# USBLiPo.net
KiCad netlist of a schematic drawn in EAGLE
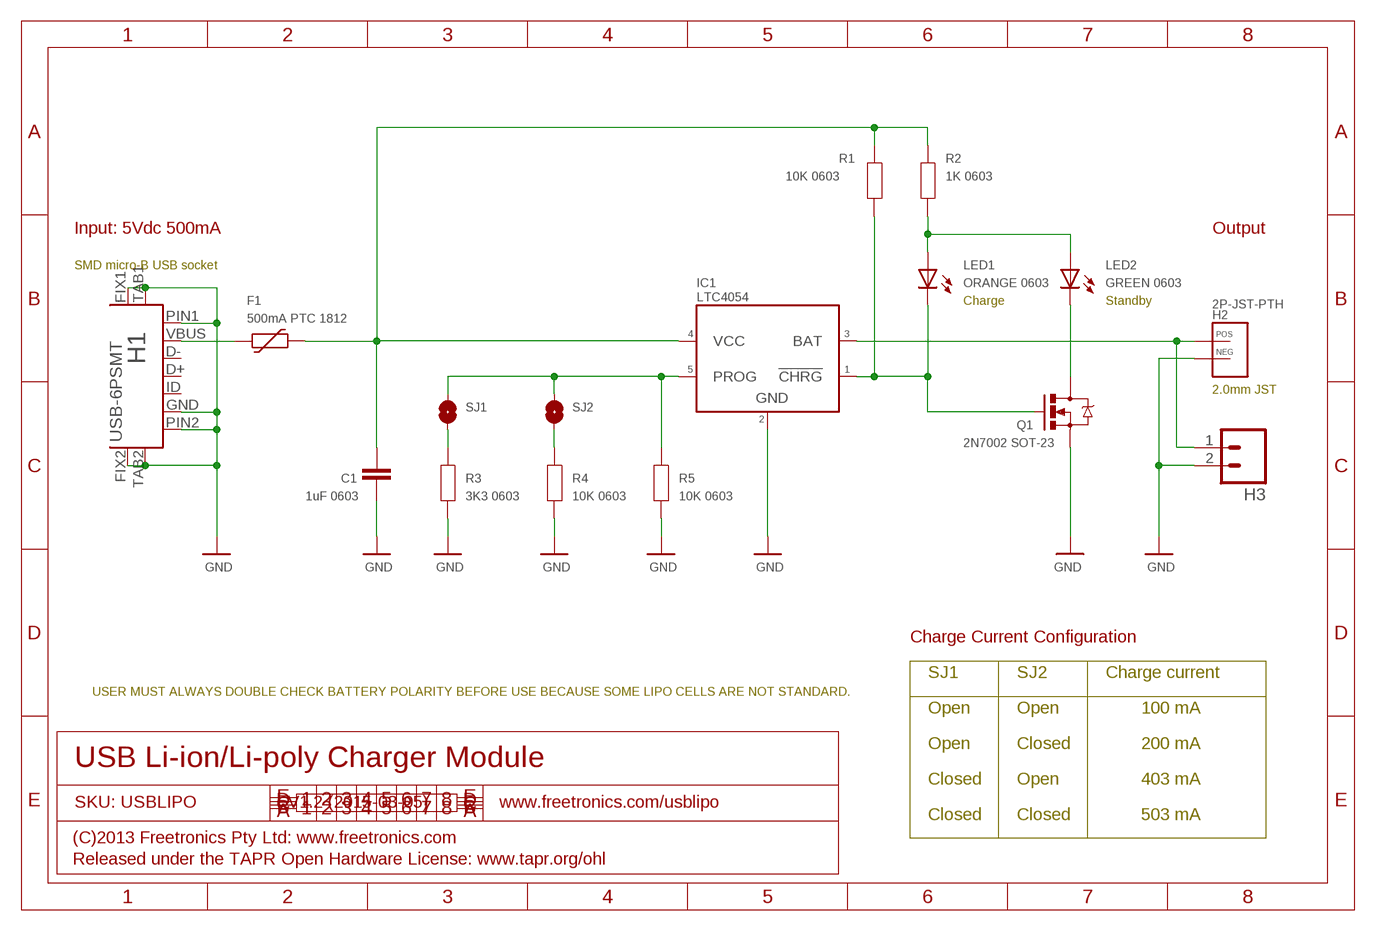
[diagram p0: schematic, sheet 1]

(export (version "E")
  (design (tool "Eeschema 10.0.6"))
  (components
    (comp (ref "C1")
      (value "1uF 0603")
      (footprint "eagle-import:0603")
      (libsource (lib "eagle-import") (part "CAP0603"))
    )
    (comp (ref "F1")
      (value "500mA PTC 1812")
      (footprint "eagle-import:1812")
      (libsource (lib "eagle-import") (part "PTC"))
    )
    (comp (ref "H1")
      (value "USB-6PSMT")
      (footprint "eagle-import:USB-MICROB-MB05PMXX")
      (libsource (lib "eagle-import") (part "USB-6PSMT"))
    )
    (comp (ref "H2")
      (value "2P-JST-PTH")
      (footprint "eagle-import:JST-2MM-TH-RA")
      (libsource (lib "eagle-import") (part "2P-JST-TH-RAPTH"))
    )
    (comp (ref "H3")
      (value "M02PTH")
      (footprint "eagle-import:1X02")
      (libsource (lib "eagle-import") (part "M02PTH"))
    )
    (comp (ref "IC1")
      (value "LTC4054")
      (footprint "eagle-import:SOT23-5")
      (libsource (lib "eagle-import") (part "LTC4054"))
    )
    (comp (ref "LED1")
      (value "ORANGE 0603")
      (footprint "eagle-import:LED-0603")
      (libsource (lib "eagle-import") (part "LED0603"))
    )
    (comp (ref "LED2")
      (value "GREEN 0603")
      (footprint "eagle-import:LED-0603")
      (libsource (lib "eagle-import") (part "LED0603"))
    )
    (comp (ref "Q1")
      (value "2N7002 SOT-23")
      (footprint "eagle-import:SOT23-3")
      (libsource (lib "eagle-import") (part "2N7002"))
    )
    (comp (ref "R1")
      (value "10K 0603")
      (footprint "eagle-import:0603")
      (libsource (lib "eagle-import") (part "RESISTOR0603"))
    )
    (comp (ref "R2")
      (value "1K 0603")
      (footprint "eagle-import:0603")
      (libsource (lib "eagle-import") (part "RESISTOR0603"))
    )
    (comp (ref "R3")
      (value "3K3 0603")
      (footprint "eagle-import:0603")
      (libsource (lib "eagle-import") (part "RESISTOR0603"))
    )
    (comp (ref "R4")
      (value "10K 0603")
      (footprint "eagle-import:0603")
      (libsource (lib "eagle-import") (part "RESISTOR0603"))
    )
    (comp (ref "R5")
      (value "10K 0603")
      (footprint "eagle-import:0603")
      (libsource (lib "eagle-import") (part "RESISTOR0603"))
    )
    (comp (ref "SJ1") (value "SJ") (footprint "eagle-import:SJ") (libsource (lib "eagle-import") (part "SJ")))
    (comp (ref "SJ2") (value "SJ") (footprint "eagle-import:SJ") (libsource (lib "eagle-import") (part "SJ")))
  )
  (nets
    (net (code "1") (name "GND") (class "Default")
      (node (ref "C1") (pin "1") (pinfunction "1_1") (pintype "passive"))
      (node (ref "H1") (pin "FIX1") (pinfunction "FIX1_FIX1") (pintype "bidirectional"))
      (node (ref "H1") (pin "FIX2") (pinfunction "FIX2_FIX2") (pintype "bidirectional"))
      (node (ref "H1") (pin "GND") (pinfunction "GND_GND") (pintype "bidirectional"))
      (node (ref "H1") (pin "PIN1") (pinfunction "PIN1_PIN1") (pintype "bidirectional"))
      (node (ref "H1") (pin "PIN2") (pinfunction "PIN2_PIN2") (pintype "bidirectional"))
      (node (ref "H1") (pin "TAB1") (pinfunction "TAB1_TAB1") (pintype "bidirectional"))
      (node (ref "H1") (pin "TAB2") (pinfunction "TAB2_TAB2") (pintype "bidirectional"))
      (node (ref "H2") (pin "NEG") (pinfunction "NEG_NEG") (pintype "power_in"))
      (node (ref "H3") (pin "2") (pinfunction "2_2") (pintype "passive"))
      (node (ref "IC1") (pin "2") (pinfunction "GND_2") (pintype "bidirectional"))
      (node (ref "Q1") (pin "2") (pinfunction "S_2") (pintype "passive"))
      (node (ref "R3") (pin "2") (pinfunction "2_2") (pintype "passive"))
      (node (ref "R4") (pin "2") (pinfunction "2_2") (pintype "passive"))
      (node (ref "R5") (pin "2") (pinfunction "2_2") (pintype "passive"))
    )
    (net (code "2") (name "Net-(F1-P$1)") (class "Default")
      (node (ref "F1") (pin "1") (pinfunction "P$1_1") (pintype "bidirectional"))
      (node (ref "H1") (pin "VBUS") (pinfunction "VBUS_VBUS") (pintype "bidirectional"))
    )
    (net (code "3") (name "Net-(F1-P$2)") (class "Default")
      (node (ref "C1") (pin "2") (pinfunction "2_2") (pintype "passive"))
      (node (ref "F1") (pin "2") (pinfunction "P$2_2") (pintype "bidirectional"))
      (node (ref "IC1") (pin "4") (pinfunction "VCC_4") (pintype "bidirectional"))
      (node (ref "R1") (pin "1") (pinfunction "1_1") (pintype "passive"))
      (node (ref "R2") (pin "1") (pinfunction "1_1") (pintype "passive"))
    )
    (net (code "4") (name "Net-(IC1-BAT)") (class "Default")
      (node (ref "H2") (pin "POS") (pinfunction "POS_POS") (pintype "power_in"))
      (node (ref "H3") (pin "1") (pinfunction "1_1") (pintype "passive"))
      (node (ref "IC1") (pin "3") (pinfunction "BAT_3") (pintype "bidirectional"))
    )
    (net (code "5") (name "Net-(IC1-PROG)") (class "Default")
      (node (ref "IC1") (pin "5") (pinfunction "PROG_5") (pintype "bidirectional"))
      (node (ref "R5") (pin "1") (pinfunction "1_1") (pintype "passive"))
      (node (ref "SJ1") (pin "2") (pinfunction "2_2") (pintype "passive"))
      (node (ref "SJ2") (pin "2") (pinfunction "2_2") (pintype "passive"))
    )
    (net (code "6") (name "Net-(IC1-~{CHRG})") (class "Default")
      (node (ref "IC1") (pin "1") (pinfunction "~{CHRG}_1") (pintype "bidirectional"))
      (node (ref "LED1") (pin "C") (pinfunction "C_C") (pintype "passive"))
      (node (ref "Q1") (pin "1") (pinfunction "G_1") (pintype "passive"))
      (node (ref "R1") (pin "2") (pinfunction "2_2") (pintype "passive"))
    )
    (net (code "7") (name "Net-(LED1-PadA)") (class "Default")
      (node (ref "LED1") (pin "A") (pinfunction "A_A") (pintype "passive"))
      (node (ref "LED2") (pin "A") (pinfunction "A_A") (pintype "passive"))
      (node (ref "R2") (pin "2") (pinfunction "2_2") (pintype "passive"))
    )
    (net (code "8") (name "Net-(Q1-D)") (class "Default")
      (node (ref "LED2") (pin "C") (pinfunction "C_C") (pintype "passive"))
      (node (ref "Q1") (pin "3") (pinfunction "D_3") (pintype "passive"))
    )
    (net (code "9") (name "Net-(R3-Pad1)") (class "Default")
      (node (ref "R3") (pin "1") (pinfunction "1_1") (pintype "passive"))
      (node (ref "SJ1") (pin "1") (pinfunction "1_1") (pintype "passive"))
    )
    (net (code "10") (name "Net-(R4-Pad1)") (class "Default")
      (node (ref "R4") (pin "1") (pinfunction "1_1") (pintype "passive"))
      (node (ref "SJ2") (pin "1") (pinfunction "1_1") (pintype "passive"))
    )
    (net (code "11") (name "unconnected-(H1-PadD+)") (class "Default")
      (node (ref "H1") (pin "D+") (pinfunction "D+_D+") (pintype "bidirectional"))
    )
    (net (code "12") (name "unconnected-(H1-PadD-)") (class "Default")
      (node (ref "H1") (pin "D-") (pinfunction "D-_D-") (pintype "bidirectional"))
    )
    (net (code "13") (name "unconnected-(H1-PadID)") (class "Default")
      (node (ref "H1") (pin "ID") (pinfunction "ID_ID") (pintype "bidirectional"))
    )
  )
)
